# L3D_Necklace_Rev1.net
KiCad netlist of a schematic drawn in EAGLE
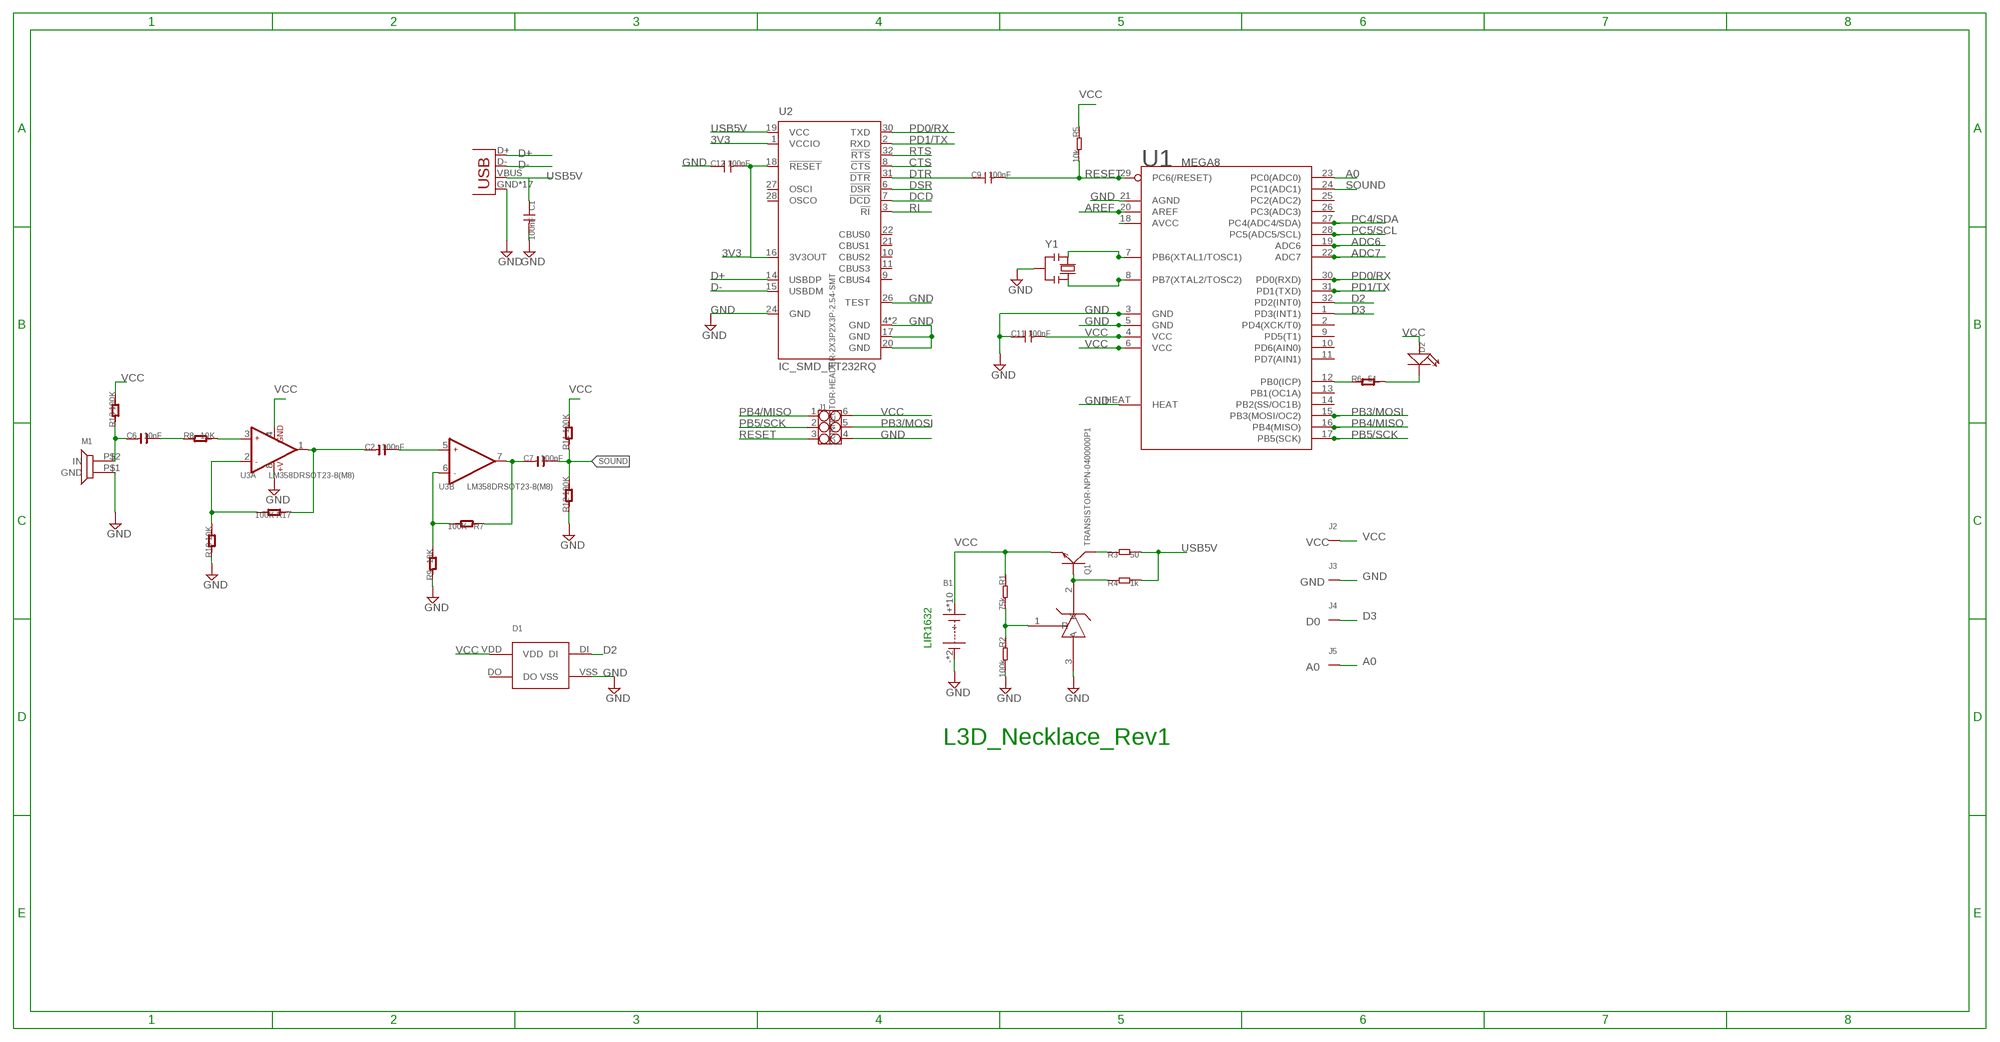
[diagram p0: schematic, sheet 1]

(export (version "E")
  (design (tool "Eeschema 10.0.6"))
  (components
    (comp (ref "B1")
      (value "BUTTONCELLLIR1632")
      (footprint "eagle-import:BUTTONCELL_LIR1632")
      (libsource (lib "eagle-import") (part "BUTTONCELLLIR1632"))
    )
    (comp (ref "C1")
      (value "100nF")
      (footprint "eagle-import:0603")
      (libsource (lib "eagle-import") (part "C-0603"))
    )
    (comp (ref "C2")
      (value "100nF")
      (footprint "eagle-import:C0603")
      (libsource (lib "eagle-import") (part "OPL Eagle Library_C-0603"))
    )
    (comp (ref "C6")
      (value "10nF")
      (footprint "eagle-import:C0603")
      (libsource (lib "eagle-import") (part "OPL Eagle Library_C-0603"))
    )
    (comp (ref "C7")
      (value "100nF")
      (footprint "eagle-import:C0603")
      (libsource (lib "eagle-import") (part "OPL Eagle Library_C-0603"))
    )
    (comp (ref "C9")
      (value "100nF")
      (footprint "eagle-import:0603")
      (libsource (lib "eagle-import") (part "C-0603"))
    )
    (comp (ref "C11")
      (value "100nF")
      (footprint "eagle-import:0603")
      (libsource (lib "eagle-import") (part "C-0603"))
    )
    (comp (ref "C12")
      (value "100nF")
      (footprint "eagle-import:0603")
      (libsource (lib "eagle-import") (part "C-0603"))
    )
    (comp (ref "D1")
      (value "WS2812BWS2812B_STANDARD")
      (footprint "eagle-import:WS2812B_STANDARD")
      (libsource (lib "eagle-import") (part "WS2812BWS2812B_STANDARD"))
    )
    (comp (ref "D2")
      (value "LEDLED1206")
      (footprint "eagle-import:LED1206")
      (libsource (lib "eagle-import") (part "LEDLED1206"))
    )
    (comp (ref "J1")
      (value "CONNECTOR-HEADER-2X3P2X3P-2.54-SMT")
      (footprint "eagle-import:2X3P-2.54-SMT")
      (libsource (lib "eagle-import") (part "CONNECTOR-HEADER-2X3P2X3P-2.54-SMT"))
    )
    (comp (ref "J2")
      (value "VCC")
      (footprint "eagle-import:1R5MM-HOLE")
      (libsource (lib "eagle-import") (part "1R5MM-HOLE"))
    )
    (comp (ref "J3")
      (value "GND")
      (footprint "eagle-import:1R5MM-HOLE")
      (libsource (lib "eagle-import") (part "1R5MM-HOLE"))
    )
    (comp (ref "J4")
      (value "D0")
      (footprint "eagle-import:1R5MM-HOLE")
      (libsource (lib "eagle-import") (part "1R5MM-HOLE"))
    )
    (comp (ref "J5")
      (value "A0")
      (footprint "eagle-import:1R5MM-HOLE")
      (libsource (lib "eagle-import") (part "1R5MM-HOLE"))
    )
    (comp (ref "JP1")
      (value "USBUSB-MICROB-SLOT-HOLE")
      (footprint "eagle-import:USB-MICROB-SLOT-HOLE")
      (libsource (lib "eagle-import") (part "USBUSB-MICROB-SLOT-HOLE"))
    )
    (comp (ref "M1")
      (value "MICROPHONEMICROPHONE_1*3MM")
      (footprint "eagle-import:MICROPHONE_1_3MM")
      (libsource (lib "eagle-import") (part "MICROPHONEMICROPHONE_13MM"))
    )
    (comp (ref "Q1")
      (value "TRANSISTOR-NPN-0400000P1")
      (footprint "eagle-import:SOT23")
      (libsource (lib "eagle-import") (part "TRANSISTOR-NPN-0400000P1"))
    )
    (comp (ref "R1")
      (value "75k")
      (footprint "eagle-import:0603")
      (libsource (lib "eagle-import") (part "R-0603"))
    )
    (comp (ref "R2")
      (value "100k")
      (footprint "eagle-import:0603")
      (libsource (lib "eagle-import") (part "R-0603"))
    )
    (comp (ref "R3")
      (value "50")
      (footprint "eagle-import:0603")
      (libsource (lib "eagle-import") (part "R-0603"))
    )
    (comp (ref "R4")
      (value "1k")
      (footprint "eagle-import:0603")
      (libsource (lib "eagle-import") (part "R-0603"))
    )
    (comp (ref "R5")
      (value "10k")
      (footprint "eagle-import:0603")
      (libsource (lib "eagle-import") (part "R-0603"))
    )
    (comp (ref "R6")
      (value "51")
      (footprint "eagle-import:R0603")
      (libsource (lib "eagle-import") (part "OPL Eagle Library_R-0603"))
    )
    (comp (ref "R7")
      (value "100K")
      (footprint "eagle-import:R0603")
      (libsource (lib "eagle-import") (part "OPL Eagle Library_R-0603"))
    )
    (comp (ref "R8")
      (value "10K")
      (footprint "eagle-import:R0603")
      (libsource (lib "eagle-import") (part "OPL Eagle Library_R-0603"))
    )
    (comp (ref "R9")
      (value "10K")
      (footprint "eagle-import:R0603")
      (libsource (lib "eagle-import") (part "OPL Eagle Library_R-0603"))
    )
    (comp (ref "R10")
      (value "10K")
      (footprint "eagle-import:R0603")
      (libsource (lib "eagle-import") (part "OPL Eagle Library_R-0603"))
    )
    (comp (ref "R11")
      (value "100K")
      (footprint "eagle-import:R0603")
      (libsource (lib "eagle-import") (part "OPL Eagle Library_R-0603"))
    )
    (comp (ref "R12")
      (value "100K")
      (footprint "eagle-import:R0603")
      (libsource (lib "eagle-import") (part "OPL Eagle Library_R-0603"))
    )
    (comp (ref "R13")
      (value "100K")
      (footprint "eagle-import:R0603")
      (libsource (lib "eagle-import") (part "OPL Eagle Library_R-0603"))
    )
    (comp (ref "R17")
      (value "100K")
      (footprint "eagle-import:R0603")
      (libsource (lib "eagle-import") (part "OPL Eagle Library_R-0603"))
    )
    (comp (ref "U1")
      (value "MEGA8")
      (footprint "eagle-import:MLF32X")
      (libsource (lib "eagle-import") (part "MEGA8"))
    )
    (comp (ref "U2")
      (value "IC_SMD_FT232RQ")
      (footprint "eagle-import:IC_SMD_QFN32")
      (libsource (lib "eagle-import") (part "IC_SMD_FT232RQ"))
    )
    (comp (ref "U3")
      (value "LM358DRSOT23-8(M8)")
      (footprint "eagle-import:SOT-23-8(M8)")
      (libsource (lib "eagle-import") (part "LM358DRSOT23-8(M8)"))
    )
    (comp (ref "Y1")
      (value "SMARTPRJ_RESONATORMU")
      (footprint "eagle-import:SMARTPRJ_RESONATOR")
      (libsource (lib "eagle-import") (part "SMARTPRJ_RESONATORMU"))
    )
    (comp (ref "Z1")
      (value "TL431")
      (footprint "eagle-import:SOT23")
      (libsource (lib "eagle-import") (part "TL431SOT23"))
    )
  )
  (nets
    (net (code "1") (name "/3V3") (class "Default")
      (node (ref "C12") (pin "2") (pinfunction "2_2") (pintype "passive"))
      (node (ref "U2") (pin "1") (pinfunction "VCCIO_1") (pintype "input"))
      (node (ref "U2") (pin "16") (pinfunction "3V3OUT_16") (pintype "input"))
      (node (ref "U2") (pin "18") (pinfunction "~{RESET}_18") (pintype "input"))
    )
    (net (code "2") (name "/A0") (class "Default")
      (node (ref "J5") (pin "P$1") (pinfunction "P$1_P$1") (pintype "bidirectional"))
      (node (ref "U1") (pin "23") (pinfunction "PC0(ADC0)_23") (pintype "bidirectional"))
    )
    (net (code "3") (name "/ADC6") (class "Default")
      (node (ref "U1") (pin "19") (pinfunction "ADC6_19") (pintype "bidirectional"))
    )
    (net (code "4") (name "/ADC7") (class "Default")
      (node (ref "U1") (pin "22") (pinfunction "ADC7_22") (pintype "bidirectional"))
    )
    (net (code "5") (name "/AREF") (class "Default")
      (node (ref "U1") (pin "20") (pinfunction "AREF_20") (pintype "bidirectional"))
    )
    (net (code "6") (name "/CTS") (class "Default")
      (node (ref "U2") (pin "8") (pinfunction "~{CTS}_8") (pintype "input"))
    )
    (net (code "7") (name "/D+") (class "Default")
      (node (ref "JP1") (pin "D+") (pinfunction "D+_D+") (pintype "bidirectional"))
      (node (ref "U2") (pin "14") (pinfunction "USBDP_14") (pintype "input"))
    )
    (net (code "8") (name "/D-") (class "Default")
      (node (ref "JP1") (pin "D-") (pinfunction "D-_D-") (pintype "bidirectional"))
      (node (ref "U2") (pin "15") (pinfunction "USBDM_15") (pintype "input"))
    )
    (net (code "9") (name "/D2") (class "Default")
      (node (ref "D1") (pin "DI") (pinfunction "DI_DI") (pintype "bidirectional"))
      (node (ref "U1") (pin "32") (pinfunction "PD2(INT0)_32") (pintype "bidirectional"))
    )
    (net (code "10") (name "/D3") (class "Default")
      (node (ref "J4") (pin "P$1") (pinfunction "P$1_P$1") (pintype "bidirectional"))
      (node (ref "U1") (pin "1") (pinfunction "PD3(INT1)_1") (pintype "bidirectional"))
    )
    (net (code "11") (name "/DCD") (class "Default")
      (node (ref "U2") (pin "7") (pinfunction "~{DCD}_7") (pintype "input"))
    )
    (net (code "12") (name "/DSR") (class "Default")
      (node (ref "U2") (pin "6") (pinfunction "~{DSR}_6") (pintype "input"))
    )
    (net (code "13") (name "/DTR") (class "Default")
      (node (ref "C9") (pin "1") (pinfunction "1_1") (pintype "passive"))
      (node (ref "U2") (pin "31") (pinfunction "~{DTR}_31") (pintype "input"))
    )
    (net (code "14") (name "/PB3{slash}MOSI") (class "Default")
      (node (ref "J1") (pin "5") (pinfunction "5_5") (pintype "bidirectional"))
      (node (ref "U1") (pin "15") (pinfunction "PB3(MOSI/OC2)_15") (pintype "bidirectional"))
    )
    (net (code "15") (name "/PB4{slash}MISO") (class "Default")
      (node (ref "J1") (pin "1") (pinfunction "1_1") (pintype "bidirectional"))
      (node (ref "U1") (pin "16") (pinfunction "PB4(MISO)_16") (pintype "bidirectional"))
    )
    (net (code "16") (name "/PB5{slash}SCK") (class "Default")
      (node (ref "J1") (pin "2") (pinfunction "2_2") (pintype "bidirectional"))
      (node (ref "U1") (pin "17") (pinfunction "PB5(SCK)_17") (pintype "bidirectional"))
    )
    (net (code "17") (name "/PC4{slash}SDA") (class "Default")
      (node (ref "U1") (pin "27") (pinfunction "PC4(ADC4/SDA)_27") (pintype "bidirectional"))
    )
    (net (code "18") (name "/PC5{slash}SCL") (class "Default")
      (node (ref "U1") (pin "28") (pinfunction "PC5(ADC5/SCL)_28") (pintype "bidirectional"))
    )
    (net (code "19") (name "/PD0{slash}RX") (class "Default")
      (node (ref "U1") (pin "30") (pinfunction "PD0(RXD)_30") (pintype "bidirectional"))
      (node (ref "U2") (pin "30") (pinfunction "TXD_30") (pintype "input"))
    )
    (net (code "20") (name "/PD1{slash}TX") (class "Default")
      (node (ref "U1") (pin "31") (pinfunction "PD1(TXD)_31") (pintype "bidirectional"))
      (node (ref "U2") (pin "2") (pinfunction "RXD_2") (pintype "input"))
    )
    (net (code "21") (name "/RESET") (class "Default")
      (node (ref "C9") (pin "2") (pinfunction "2_2") (pintype "passive"))
      (node (ref "J1") (pin "3") (pinfunction "3_3") (pintype "bidirectional"))
      (node (ref "R5") (pin "2") (pinfunction "2_2") (pintype "passive"))
      (node (ref "U1") (pin "29") (pinfunction "PC6(/RESET)_29") (pintype "bidirectional"))
    )
    (net (code "22") (name "/RI") (class "Default")
      (node (ref "U2") (pin "3") (pinfunction "~{RI}_3") (pintype "input"))
    )
    (net (code "23") (name "/RTS") (class "Default")
      (node (ref "U2") (pin "32") (pinfunction "~{RTS}_32") (pintype "input"))
    )
    (net (code "24") (name "/USB5V") (class "Default")
      (node (ref "C1") (pin "1") (pinfunction "1_1") (pintype "passive"))
      (node (ref "JP1") (pin "VBUS") (pinfunction "VBUS_VBUS") (pintype "bidirectional"))
      (node (ref "R3") (pin "2") (pinfunction "2_2") (pintype "passive"))
      (node (ref "R4") (pin "2") (pinfunction "2_2") (pintype "passive"))
      (node (ref "U2") (pin "19") (pinfunction "VCC_19") (pintype "input"))
    )
    (net (code "25") (name "/VCC") (class "Default")
      (node (ref "B1") (pin "+") (pinfunction "+_+") (pintype "bidirectional"))
      (node (ref "B1") (pin "+1'") (pinfunction "+_+1'") (pintype "bidirectional"))
      (node (ref "B1") (pin "P$10") (pinfunction "+_P$10") (pintype "bidirectional"))
      (node (ref "B1") (pin "P$3") (pinfunction "+_P$3") (pintype "bidirectional"))
      (node (ref "B1") (pin "P$4") (pinfunction "+_P$4") (pintype "bidirectional"))
      (node (ref "B1") (pin "P$5") (pinfunction "+_P$5") (pintype "bidirectional"))
      (node (ref "B1") (pin "P$6") (pinfunction "+_P$6") (pintype "bidirectional"))
      (node (ref "B1") (pin "P$7") (pinfunction "+_P$7") (pintype "bidirectional"))
      (node (ref "B1") (pin "P$8") (pinfunction "+_P$8") (pintype "bidirectional"))
      (node (ref "B1") (pin "P$9") (pinfunction "+_P$9") (pintype "bidirectional"))
      (node (ref "C11") (pin "2") (pinfunction "2_2") (pintype "passive"))
      (node (ref "D1") (pin "VDD") (pinfunction "VDD_VDD") (pintype "bidirectional"))
      (node (ref "D2") (pin "+") (pinfunction "+_+") (pintype "passive"))
      (node (ref "J1") (pin "6") (pinfunction "6_6") (pintype "bidirectional"))
      (node (ref "J2") (pin "P$1") (pinfunction "P$1_P$1") (pintype "bidirectional"))
      (node (ref "Q1") (pin "2") (pinfunction "E_2") (pintype "passive"))
      (node (ref "R1") (pin "1") (pinfunction "1_1") (pintype "passive"))
      (node (ref "R11") (pin "2") (pinfunction "2_2") (pintype "bidirectional"))
      (node (ref "R13") (pin "2") (pinfunction "2_2") (pintype "bidirectional"))
      (node (ref "R5") (pin "1") (pinfunction "1_1") (pintype "passive"))
      (node (ref "U1") (pin "18") (pinfunction "AVCC_18") (pintype "bidirectional"))
      (node (ref "U1") (pin "4") (pinfunction "VCC_4") (pintype "bidirectional"))
      (node (ref "U1") (pin "6") (pinfunction "VCC_6") (pintype "bidirectional"))
      (node (ref "U3") (pin "4") (pinfunction "GND_4") (pintype "power_in"))
    )
    (net (code "26") (name "GND") (class "Default")
      (node (ref "B1") (pin "-") (pinfunction "-_-") (pintype "bidirectional"))
      (node (ref "B1") (pin "-'") (pinfunction "-_-'") (pintype "bidirectional"))
      (node (ref "C1") (pin "2") (pinfunction "2_2") (pintype "passive"))
      (node (ref "C11") (pin "1") (pinfunction "1_1") (pintype "passive"))
      (node (ref "C12") (pin "1") (pinfunction "1_1") (pintype "passive"))
      (node (ref "D1") (pin "VSS") (pinfunction "VSS_VSS") (pintype "bidirectional"))
      (node (ref "J1") (pin "4") (pinfunction "4_4") (pintype "bidirectional"))
      (node (ref "J3") (pin "P$1") (pinfunction "P$1_P$1") (pintype "bidirectional"))
      (node (ref "JP1") (pin "GND") (pinfunction "GND_GND") (pintype "bidirectional"))
      (node (ref "JP1") (pin "MT1") (pinfunction "GND_MT1") (pintype "bidirectional"))
      (node (ref "JP1") (pin "MT10") (pinfunction "GND_MT10") (pintype "bidirectional"))
      (node (ref "JP1") (pin "MT11") (pinfunction "GND_MT11") (pintype "bidirectional"))
      (node (ref "JP1") (pin "MT12") (pinfunction "GND_MT12") (pintype "bidirectional"))
      (node (ref "JP1") (pin "MT2") (pinfunction "GND_MT2") (pintype "bidirectional"))
      (node (ref "JP1") (pin "MT3") (pinfunction "GND_MT3") (pintype "bidirectional"))
      (node (ref "JP1") (pin "MT4") (pinfunction "GND_MT4") (pintype "bidirectional"))
      (node (ref "JP1") (pin "MT5") (pinfunction "GND_MT5") (pintype "bidirectional"))
      (node (ref "JP1") (pin "MT6") (pinfunction "GND_MT6") (pintype "bidirectional"))
      (node (ref "JP1") (pin "MT7") (pinfunction "GND_MT7") (pintype "bidirectional"))
      (node (ref "JP1") (pin "MT8") (pinfunction "GND_MT8") (pintype "bidirectional"))
      (node (ref "JP1") (pin "MT9") (pinfunction "GND_MT9") (pintype "bidirectional"))
      (node (ref "JP1") (pin "P$1") (pinfunction "GND_P$1") (pintype "bidirectional"))
      (node (ref "JP1") (pin "P$2") (pinfunction "GND_P$2") (pintype "bidirectional"))
      (node (ref "JP1") (pin "P$3") (pinfunction "GND_P$3") (pintype "bidirectional"))
      (node (ref "JP1") (pin "P$4") (pinfunction "GND_P$4") (pintype "bidirectional"))
      (node (ref "M1") (pin "P$1") (pinfunction "GND_P$1") (pintype "bidirectional"))
      (node (ref "R10") (pin "1") (pinfunction "1_1") (pintype "bidirectional"))
      (node (ref "R12") (pin "1") (pinfunction "1_1") (pintype "bidirectional"))
      (node (ref "R2") (pin "2") (pinfunction "2_2") (pintype "passive"))
      (node (ref "R9") (pin "1") (pinfunction "1_1") (pintype "bidirectional"))
      (node (ref "U1") (pin "21") (pinfunction "AGND_21") (pintype "bidirectional"))
      (node (ref "U1") (pin "3") (pinfunction "GND_3") (pintype "bidirectional"))
      (node (ref "U1") (pin "5") (pinfunction "GND_5") (pintype "bidirectional"))
      (node (ref "U1") (pin "HEAT") (pinfunction "HEAT_HEAT") (pintype "bidirectional"))
      (node (ref "U2") (pin "17") (pinfunction "GND_17") (pintype "input"))
      (node (ref "U2") (pin "20") (pinfunction "GND_20") (pintype "input"))
      (node (ref "U2") (pin "24") (pinfunction "GND_24") (pintype "input"))
      (node (ref "U2") (pin "26") (pinfunction "TEST_26") (pintype "input"))
      (node (ref "U2") (pin "4") (pinfunction "GND_4") (pintype "input"))
      (node (ref "U2") (pin "EXP") (pinfunction "GND_EXP") (pintype "input"))
      (node (ref "U3") (pin "8") (pinfunction "+V_8") (pintype "power_in"))
      (node (ref "Y1") (pin "2") (pinfunction "2_2") (pintype "passive"))
      (node (ref "Z1") (pin "3") (pinfunction "A_3") (pintype "bidirectional"))
    )
    (net (code "27") (name "Net-(C6-Pad2)") (class "Default")
      (node (ref "C6") (pin "2") (pinfunction "2_2") (pintype "bidirectional"))
      (node (ref "R8") (pin "1") (pinfunction "1_1") (pintype "bidirectional"))
    )
    (net (code "28") (name "Net-(D2-Pad-)") (class "Default")
      (node (ref "D2") (pin "-") (pinfunction "-_-") (pintype "passive"))
      (node (ref "R6") (pin "2") (pinfunction "2_2") (pintype "bidirectional"))
    )
    (net (code "29") (name "Net-(M1-IN)") (class "Default")
      (node (ref "C6") (pin "1") (pinfunction "1_1") (pintype "bidirectional"))
      (node (ref "M1") (pin "P$2") (pinfunction "IN_P$2") (pintype "bidirectional"))
      (node (ref "R13") (pin "1") (pinfunction "1_1") (pintype "bidirectional"))
    )
    (net (code "30") (name "Net-(Q1-B)") (class "Default")
      (node (ref "Q1") (pin "1") (pinfunction "B_1") (pintype "passive"))
      (node (ref "R4") (pin "1") (pinfunction "1_1") (pintype "passive"))
      (node (ref "Z1") (pin "2") (pinfunction "K_2") (pintype "bidirectional"))
    )
    (net (code "31") (name "Net-(Q1-C)") (class "Default")
      (node (ref "Q1") (pin "3") (pinfunction "C_3") (pintype "passive"))
      (node (ref "R3") (pin "1") (pinfunction "1_1") (pintype "passive"))
    )
    (net (code "32") (name "Net-(U1-PB0(ICP))") (class "Default")
      (node (ref "R6") (pin "1") (pinfunction "1_1") (pintype "bidirectional"))
      (node (ref "U1") (pin "12") (pinfunction "PB0(ICP)_12") (pintype "bidirectional"))
    )
    (net (code "33") (name "Net-(U1-PB6(XTAL1{slash}TOSC1))") (class "Default")
      (node (ref "U1") (pin "7") (pinfunction "PB6(XTAL1/TOSC1)_7") (pintype "bidirectional"))
      (node (ref "Y1") (pin "1") (pinfunction "1_1") (pintype "passive"))
    )
    (net (code "34") (name "Net-(U1-PB7(XTAL2{slash}TOSC2))") (class "Default")
      (node (ref "U1") (pin "8") (pinfunction "PB7(XTAL2/TOSC2)_8") (pintype "bidirectional"))
      (node (ref "Y1") (pin "3") (pinfunction "3_3") (pintype "passive"))
    )
    (net (code "35") (name "Net-(U3A-+IN1)") (class "Default")
      (node (ref "R8") (pin "2") (pinfunction "2_2") (pintype "bidirectional"))
      (node (ref "U3") (pin "3") (pinfunction "+IN1_3") (pintype "input"))
    )
    (net (code "36") (name "Net-(U3A--IN1)") (class "Default")
      (node (ref "R10") (pin "2") (pinfunction "2_2") (pintype "bidirectional"))
      (node (ref "R17") (pin "2") (pinfunction "2_2") (pintype "bidirectional"))
      (node (ref "U3") (pin "2") (pinfunction "-IN1_2") (pintype "input"))
    )
    (net (code "37") (name "Net-(U3A-OUT1)") (class "Default")
      (node (ref "C2") (pin "1") (pinfunction "1_1") (pintype "bidirectional"))
      (node (ref "R17") (pin "1") (pinfunction "1_1") (pintype "bidirectional"))
      (node (ref "U3") (pin "1") (pinfunction "OUT1_1") (pintype "output"))
    )
    (net (code "38") (name "Net-(U3B-+IN2)") (class "Default")
      (node (ref "C2") (pin "2") (pinfunction "2_2") (pintype "bidirectional"))
      (node (ref "U3") (pin "5") (pinfunction "+IN2_5") (pintype "input"))
    )
    (net (code "39") (name "Net-(U3B--IN2)") (class "Default")
      (node (ref "R7") (pin "2") (pinfunction "2_2") (pintype "bidirectional"))
      (node (ref "R9") (pin "2") (pinfunction "2_2") (pintype "bidirectional"))
      (node (ref "U3") (pin "6") (pinfunction "-IN2_6") (pintype "input"))
    )
    (net (code "40") (name "Net-(U3B-OUT2)") (class "Default")
      (node (ref "C7") (pin "1") (pinfunction "1_1") (pintype "bidirectional"))
      (node (ref "R7") (pin "1") (pinfunction "1_1") (pintype "bidirectional"))
      (node (ref "U3") (pin "7") (pinfunction "OUT2_7") (pintype "output"))
    )
    (net (code "41") (name "Net-(Z1-R)") (class "Default")
      (node (ref "R1") (pin "2") (pinfunction "2_2") (pintype "passive"))
      (node (ref "R2") (pin "1") (pinfunction "1_1") (pintype "passive"))
      (node (ref "Z1") (pin "1") (pinfunction "R_1") (pintype "bidirectional"))
    )
    (net (code "42") (name "SOUND") (class "Default")
      (node (ref "C7") (pin "2") (pinfunction "2_2") (pintype "bidirectional"))
      (node (ref "R11") (pin "1") (pinfunction "1_1") (pintype "bidirectional"))
      (node (ref "R12") (pin "2") (pinfunction "2_2") (pintype "bidirectional"))
      (node (ref "U1") (pin "24") (pinfunction "PC1(ADC1)_24") (pintype "bidirectional"))
    )
    (net (code "43") (name "unconnected-(D1-PadDO)") (class "Default")
      (node (ref "D1") (pin "DO") (pinfunction "DO_DO") (pintype "bidirectional"))
    )
    (net (code "44") (name "unconnected-(U1-PB1(OC1A)-Pad13)") (class "Default")
      (node (ref "U1") (pin "13") (pinfunction "PB1(OC1A)_13") (pintype "bidirectional"))
    )
    (net (code "45") (name "unconnected-(U1-PB2(SS{slash}OC1B)-Pad14)") (class "Default")
      (node (ref "U1") (pin "14") (pinfunction "PB2(SS/OC1B)_14") (pintype "bidirectional"))
    )
    (net (code "46") (name "unconnected-(U1-PC2(ADC2)-Pad25)") (class "Default")
      (node (ref "U1") (pin "25") (pinfunction "PC2(ADC2)_25") (pintype "bidirectional"))
    )
    (net (code "47") (name "unconnected-(U1-PC3(ADC3)-Pad26)") (class "Default")
      (node (ref "U1") (pin "26") (pinfunction "PC3(ADC3)_26") (pintype "bidirectional"))
    )
    (net (code "48") (name "unconnected-(U1-PD4(XCK{slash}T0)-Pad2)") (class "Default")
      (node (ref "U1") (pin "2") (pinfunction "PD4(XCK/T0)_2") (pintype "bidirectional"))
    )
    (net (code "49") (name "unconnected-(U1-PD5(T1)-Pad9)") (class "Default")
      (node (ref "U1") (pin "9") (pinfunction "PD5(T1)_9") (pintype "bidirectional"))
    )
    (net (code "50") (name "unconnected-(U1-PD6(AIN0)-Pad10)") (class "Default")
      (node (ref "U1") (pin "10") (pinfunction "PD6(AIN0)_10") (pintype "bidirectional"))
    )
    (net (code "51") (name "unconnected-(U1-PD7(AIN1)-Pad11)") (class "Default")
      (node (ref "U1") (pin "11") (pinfunction "PD7(AIN1)_11") (pintype "bidirectional"))
    )
    (net (code "52") (name "unconnected-(U2-CBUS0-Pad22)") (class "Default")
      (node (ref "U2") (pin "22") (pinfunction "CBUS0_22") (pintype "input"))
    )
    (net (code "53") (name "unconnected-(U2-CBUS1-Pad21)") (class "Default")
      (node (ref "U2") (pin "21") (pinfunction "CBUS1_21") (pintype "input"))
    )
    (net (code "54") (name "unconnected-(U2-CBUS2-Pad10)") (class "Default")
      (node (ref "U2") (pin "10") (pinfunction "CBUS2_10") (pintype "input"))
    )
    (net (code "55") (name "unconnected-(U2-CBUS3-Pad11)") (class "Default")
      (node (ref "U2") (pin "11") (pinfunction "CBUS3_11") (pintype "input"))
    )
    (net (code "56") (name "unconnected-(U2-CBUS4-Pad9)") (class "Default")
      (node (ref "U2") (pin "9") (pinfunction "CBUS4_9") (pintype "input"))
    )
    (net (code "57") (name "unconnected-(U2-OSCI-Pad27)") (class "Default")
      (node (ref "U2") (pin "27") (pinfunction "OSCI_27") (pintype "input"))
    )
    (net (code "58") (name "unconnected-(U2-OSCO-Pad28)") (class "Default")
      (node (ref "U2") (pin "28") (pinfunction "OSCO_28") (pintype "input"))
    )
  )
)
